# arduinoModuleLB.net
KiCad netlist of a schematic drawn in EAGLE
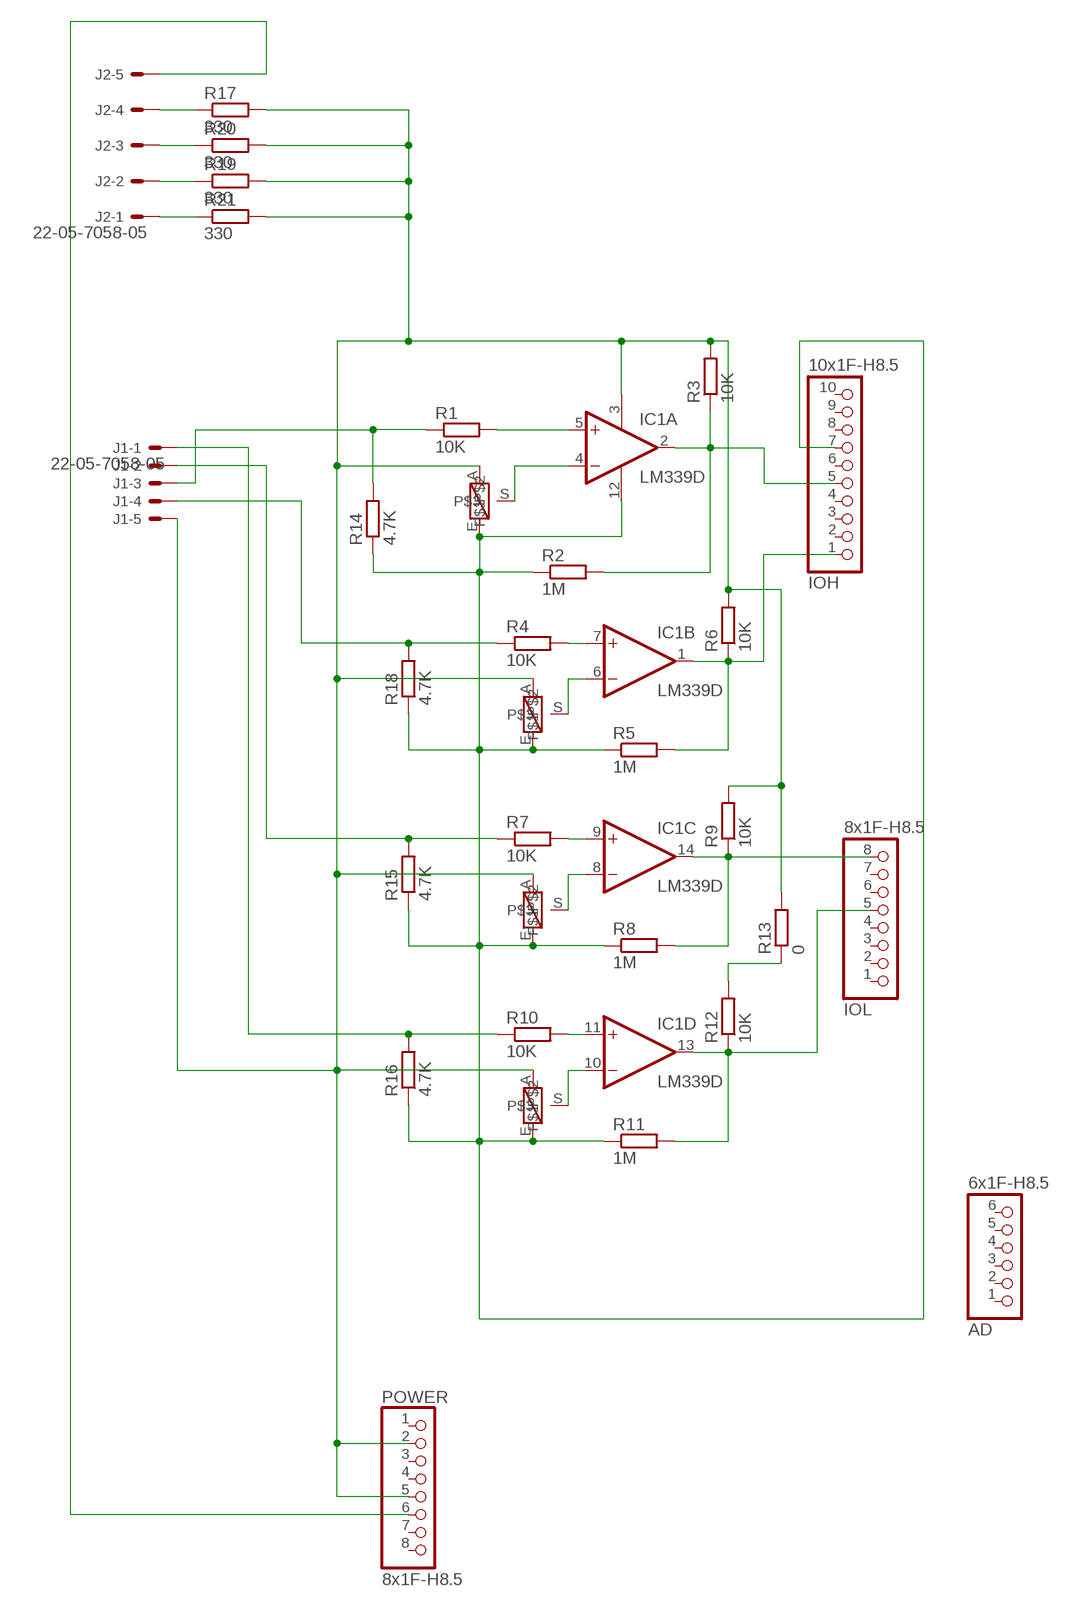
[diagram p0: schematic, sheet 1]

(export (version "E")
  (design (tool "Eeschema 10.0.6"))
  (components
    (comp (ref "AD")
      (value "6x1F-H8.5")
      (footprint "eagle-import:SMARTPRJ_1X06")
      (libsource (lib "eagle-import") (part "SMARTPRJ_PINHD-1X6"))
    )
    (comp (ref "IC1")
      (value "LM339D")
      (footprint "eagle-import:SO14")
      (libsource (lib "eagle-import") (part "LM339D"))
    )
    (comp (ref "IOH")
      (value "10x1F-H8.5")
      (footprint "eagle-import:SMARTPRJ_1X10")
      (libsource (lib "eagle-import") (part "SMARTPRJ_PINHD-1X10_ARD"))
    )
    (comp (ref "IOL")
      (value "8x1F-H8.5")
      (footprint "eagle-import:SMARTPRJ_1X08")
      (libsource (lib "eagle-import") (part "SMARTPRJ_PINHD-1X8"))
    )
    (comp (ref "J1")
      (value "22-05-7058-05")
      (footprint "eagle-import:7395-05")
      (libsource (lib "eagle-import") (part "22-?-0505-7058"))
    )
    (comp (ref "J2")
      (value "22-05-7058-05")
      (footprint "eagle-import:7395-05")
      (libsource (lib "eagle-import") (part "22-?-0505-7058"))
    )
    (comp (ref "POWER")
      (value "8x1F-H8.5")
      (footprint "eagle-import:SMARTPRJ_1X08")
      (libsource (lib "eagle-import") (part "SMARTPRJ_PINHD-1X8"))
    )
    (comp (ref "R1")
      (value "10K")
      (footprint "eagle-import:R0603")
      (libsource (lib "eagle-import") (part "R-EU_R0603"))
    )
    (comp (ref "R2")
      (value "1M")
      (footprint "eagle-import:R0603")
      (libsource (lib "eagle-import") (part "R-EU_R0603"))
    )
    (comp (ref "R3")
      (value "10K")
      (footprint "eagle-import:R0603")
      (libsource (lib "eagle-import") (part "R-EU_R0603"))
    )
    (comp (ref "R4")
      (value "10K")
      (footprint "eagle-import:R0603")
      (libsource (lib "eagle-import") (part "R-EU_R0603"))
    )
    (comp (ref "R5")
      (value "1M")
      (footprint "eagle-import:R0603")
      (libsource (lib "eagle-import") (part "R-EU_R0603"))
    )
    (comp (ref "R6")
      (value "10K")
      (footprint "eagle-import:R0603")
      (libsource (lib "eagle-import") (part "R-EU_R0603"))
    )
    (comp (ref "R7")
      (value "10K")
      (footprint "eagle-import:R0603")
      (libsource (lib "eagle-import") (part "R-EU_R0603"))
    )
    (comp (ref "R8")
      (value "1M")
      (footprint "eagle-import:R0603")
      (libsource (lib "eagle-import") (part "R-EU_R0603"))
    )
    (comp (ref "R9")
      (value "10K")
      (footprint "eagle-import:R0603")
      (libsource (lib "eagle-import") (part "R-EU_R0603"))
    )
    (comp (ref "R10")
      (value "10K")
      (footprint "eagle-import:R0603")
      (libsource (lib "eagle-import") (part "R-EU_R0603"))
    )
    (comp (ref "R11")
      (value "1M")
      (footprint "eagle-import:R0603")
      (libsource (lib "eagle-import") (part "R-EU_R0603"))
    )
    (comp (ref "R12")
      (value "10K")
      (footprint "eagle-import:R0603")
      (libsource (lib "eagle-import") (part "R-EU_R0603"))
    )
    (comp (ref "R13")
      (value "0")
      (footprint "eagle-import:0207_10")
      (libsource (lib "eagle-import") (part "R-EU_0207/10"))
    )
    (comp (ref "R14")
      (value "4.7K")
      (footprint "eagle-import:0207_10")
      (libsource (lib "eagle-import") (part "R-EU_0207/10"))
    )
    (comp (ref "R15")
      (value "4.7K")
      (footprint "eagle-import:0207_10")
      (libsource (lib "eagle-import") (part "R-EU_0207/10"))
    )
    (comp (ref "R16")
      (value "4.7K")
      (footprint "eagle-import:0207_10")
      (libsource (lib "eagle-import") (part "R-EU_0207/10"))
    )
    (comp (ref "R17")
      (value "330")
      (footprint "eagle-import:R0603")
      (libsource (lib "eagle-import") (part "R-EU_R0603"))
    )
    (comp (ref "R18")
      (value "4.7K")
      (footprint "eagle-import:0207_10")
      (libsource (lib "eagle-import") (part "R-EU_0207/10"))
    )
    (comp (ref "R19")
      (value "330")
      (footprint "eagle-import:R0603")
      (libsource (lib "eagle-import") (part "R-EU_R0603"))
    )
    (comp (ref "R20")
      (value "330")
      (footprint "eagle-import:R0603")
      (libsource (lib "eagle-import") (part "R-EU_R0603"))
    )
    (comp (ref "R21")
      (value "330")
      (footprint "eagle-import:R0603")
      (libsource (lib "eagle-import") (part "R-EU_R0603"))
    )
    (comp (ref "U$3")
      (value "M64P103KB40")
      (footprint "eagle-import:M64P")
      (libsource (lib "eagle-import") (part "M64P103KB40"))
    )
    (comp (ref "U$4")
      (value "M64P103KB40")
      (footprint "eagle-import:M64P")
      (libsource (lib "eagle-import") (part "M64P103KB40"))
    )
    (comp (ref "U$5")
      (value "M64P103KB40")
      (footprint "eagle-import:M64P")
      (libsource (lib "eagle-import") (part "M64P103KB40"))
    )
    (comp (ref "U$6")
      (value "M64P103KB40")
      (footprint "eagle-import:M64P")
      (libsource (lib "eagle-import") (part "M64P103KB40"))
    )
  )
  (nets
    (net (code "1") (name "Net-(IC1A-+IN)") (class "Default")
      (node (ref "IC1") (pin "5") (pinfunction "+IN_5") (pintype "input"))
      (node (ref "R1") (pin "2") (pinfunction "2_2") (pintype "passive"))
    )
    (net (code "2") (name "Net-(IC1A--IN)") (class "Default")
      (node (ref "IC1") (pin "4") (pinfunction "-IN_4") (pintype "input"))
      (node (ref "U$4") (pin "S") (pinfunction "P$3_S") (pintype "bidirectional"))
    )
    (net (code "3") (name "Net-(IC1A-OUT)") (class "Default")
      (node (ref "IC1") (pin "2") (pinfunction "OUT_2") (pintype "open_collector"))
      (node (ref "IOH") (pin "5") (pinfunction "5_5") (pintype "passive"))
      (node (ref "R2") (pin "2") (pinfunction "2_2") (pintype "passive"))
      (node (ref "R3") (pin "1") (pinfunction "1_1") (pintype "passive"))
    )
    (net (code "4") (name "Net-(IC1B-+IN)") (class "Default")
      (node (ref "IC1") (pin "7") (pinfunction "+IN_7") (pintype "input"))
      (node (ref "R4") (pin "2") (pinfunction "2_2") (pintype "passive"))
    )
    (net (code "5") (name "Net-(IC1B--IN)") (class "Default")
      (node (ref "IC1") (pin "6") (pinfunction "-IN_6") (pintype "input"))
      (node (ref "U$3") (pin "S") (pinfunction "P$3_S") (pintype "bidirectional"))
    )
    (net (code "6") (name "Net-(IC1B-OUT)") (class "Default")
      (node (ref "IC1") (pin "1") (pinfunction "OUT_1") (pintype "open_collector"))
      (node (ref "IOH") (pin "1") (pinfunction "1_1") (pintype "passive"))
      (node (ref "R5") (pin "2") (pinfunction "2_2") (pintype "passive"))
      (node (ref "R6") (pin "1") (pinfunction "1_1") (pintype "passive"))
    )
    (net (code "7") (name "Net-(IC1C-+IN)") (class "Default")
      (node (ref "IC1") (pin "9") (pinfunction "+IN_9") (pintype "input"))
      (node (ref "R7") (pin "2") (pinfunction "2_2") (pintype "passive"))
    )
    (net (code "8") (name "Net-(IC1C--IN)") (class "Default")
      (node (ref "IC1") (pin "8") (pinfunction "-IN_8") (pintype "input"))
      (node (ref "U$5") (pin "S") (pinfunction "P$3_S") (pintype "bidirectional"))
    )
    (net (code "9") (name "Net-(IC1C-OUT)") (class "Default")
      (node (ref "IC1") (pin "14") (pinfunction "OUT_14") (pintype "open_collector"))
      (node (ref "IOL") (pin "8") (pinfunction "8_8") (pintype "passive"))
      (node (ref "R8") (pin "2") (pinfunction "2_2") (pintype "passive"))
      (node (ref "R9") (pin "1") (pinfunction "1_1") (pintype "passive"))
    )
    (net (code "10") (name "Net-(IC1D-+IN)") (class "Default")
      (node (ref "IC1") (pin "11") (pinfunction "+IN_11") (pintype "input"))
      (node (ref "R10") (pin "2") (pinfunction "2_2") (pintype "passive"))
    )
    (net (code "11") (name "Net-(IC1D--IN)") (class "Default")
      (node (ref "IC1") (pin "10") (pinfunction "-IN_10") (pintype "input"))
      (node (ref "U$6") (pin "S") (pinfunction "P$3_S") (pintype "bidirectional"))
    )
    (net (code "12") (name "Net-(IC1D-OUT)") (class "Default")
      (node (ref "IC1") (pin "13") (pinfunction "OUT_13") (pintype "open_collector"))
      (node (ref "IOL") (pin "5") (pinfunction "5_5") (pintype "passive"))
      (node (ref "R11") (pin "2") (pinfunction "2_2") (pintype "passive"))
      (node (ref "R12") (pin "1") (pinfunction "1_1") (pintype "passive"))
    )
    (net (code "13") (name "Net-(IC1E-GND)") (class "Default")
      (node (ref "IC1") (pin "12") (pinfunction "GND_12") (pintype "power_in"))
      (node (ref "IOH") (pin "7") (pinfunction "7_7") (pintype "passive"))
      (node (ref "R11") (pin "1") (pinfunction "1_1") (pintype "passive"))
      (node (ref "R14") (pin "1") (pinfunction "1_1") (pintype "passive"))
      (node (ref "R15") (pin "1") (pinfunction "1_1") (pintype "passive"))
      (node (ref "R16") (pin "1") (pinfunction "1_1") (pintype "passive"))
      (node (ref "R18") (pin "1") (pinfunction "1_1") (pintype "passive"))
      (node (ref "R2") (pin "1") (pinfunction "1_1") (pintype "passive"))
      (node (ref "R5") (pin "1") (pinfunction "1_1") (pintype "passive"))
      (node (ref "R8") (pin "1") (pinfunction "1_1") (pintype "passive"))
      (node (ref "U$3") (pin "E") (pinfunction "P$2_E") (pintype "bidirectional"))
      (node (ref "U$4") (pin "E") (pinfunction "P$2_E") (pintype "bidirectional"))
      (node (ref "U$5") (pin "E") (pinfunction "P$2_E") (pintype "bidirectional"))
      (node (ref "U$6") (pin "E") (pinfunction "P$2_E") (pintype "bidirectional"))
    )
    (net (code "14") (name "Net-(IC1E-V+)") (class "Default")
      (node (ref "IC1") (pin "3") (pinfunction "V+_3") (pintype "power_in"))
      (node (ref "J1") (pin "5") (pinfunction "S_5") (pintype "passive"))
      (node (ref "POWER") (pin "2") (pinfunction "2_2") (pintype "passive"))
      (node (ref "POWER") (pin "5") (pinfunction "5_5") (pintype "passive"))
      (node (ref "R13") (pin "2") (pinfunction "2_2") (pintype "passive"))
      (node (ref "R17") (pin "2") (pinfunction "2_2") (pintype "passive"))
      (node (ref "R19") (pin "2") (pinfunction "2_2") (pintype "passive"))
      (node (ref "R20") (pin "2") (pinfunction "2_2") (pintype "passive"))
      (node (ref "R21") (pin "2") (pinfunction "2_2") (pintype "passive"))
      (node (ref "R3") (pin "2") (pinfunction "2_2") (pintype "passive"))
      (node (ref "R6") (pin "2") (pinfunction "2_2") (pintype "passive"))
      (node (ref "R9") (pin "2") (pinfunction "2_2") (pintype "passive"))
      (node (ref "U$3") (pin "A") (pinfunction "P$1_A") (pintype "bidirectional"))
      (node (ref "U$4") (pin "A") (pinfunction "P$1_A") (pintype "bidirectional"))
      (node (ref "U$5") (pin "A") (pinfunction "P$1_A") (pintype "bidirectional"))
      (node (ref "U$6") (pin "A") (pinfunction "P$1_A") (pintype "bidirectional"))
    )
    (net (code "15") (name "Net-(J1A-S)") (class "Default")
      (node (ref "J1") (pin "1") (pinfunction "S_1") (pintype "passive"))
      (node (ref "R10") (pin "1") (pinfunction "1_1") (pintype "passive"))
      (node (ref "R16") (pin "2") (pinfunction "2_2") (pintype "passive"))
    )
    (net (code "16") (name "Net-(J1B-S)") (class "Default")
      (node (ref "J1") (pin "2") (pinfunction "S_2") (pintype "passive"))
      (node (ref "R15") (pin "2") (pinfunction "2_2") (pintype "passive"))
      (node (ref "R7") (pin "1") (pinfunction "1_1") (pintype "passive"))
    )
    (net (code "17") (name "Net-(J1C-S)") (class "Default")
      (node (ref "J1") (pin "3") (pinfunction "S_3") (pintype "passive"))
      (node (ref "R1") (pin "1") (pinfunction "1_1") (pintype "passive"))
      (node (ref "R14") (pin "2") (pinfunction "2_2") (pintype "passive"))
    )
    (net (code "18") (name "Net-(J1D-S)") (class "Default")
      (node (ref "J1") (pin "4") (pinfunction "S_4") (pintype "passive"))
      (node (ref "R18") (pin "2") (pinfunction "2_2") (pintype "passive"))
      (node (ref "R4") (pin "1") (pinfunction "1_1") (pintype "passive"))
    )
    (net (code "19") (name "Net-(J2A-S)") (class "Default")
      (node (ref "J2") (pin "1") (pinfunction "S_1") (pintype "passive"))
      (node (ref "R21") (pin "1") (pinfunction "1_1") (pintype "passive"))
    )
    (net (code "20") (name "Net-(J2B-S)") (class "Default")
      (node (ref "J2") (pin "2") (pinfunction "S_2") (pintype "passive"))
      (node (ref "R19") (pin "1") (pinfunction "1_1") (pintype "passive"))
    )
    (net (code "21") (name "Net-(J2C-S)") (class "Default")
      (node (ref "J2") (pin "3") (pinfunction "S_3") (pintype "passive"))
      (node (ref "R20") (pin "1") (pinfunction "1_1") (pintype "passive"))
    )
    (net (code "22") (name "Net-(J2D-S)") (class "Default")
      (node (ref "J2") (pin "4") (pinfunction "S_4") (pintype "passive"))
      (node (ref "R17") (pin "1") (pinfunction "1_1") (pintype "passive"))
    )
    (net (code "23") (name "Net-(J2E-S)") (class "Default")
      (node (ref "J2") (pin "5") (pinfunction "S_5") (pintype "passive"))
      (node (ref "POWER") (pin "6") (pinfunction "6_6") (pintype "passive"))
    )
    (net (code "24") (name "Net-(R12-Pad2)") (class "Default")
      (node (ref "R12") (pin "2") (pinfunction "2_2") (pintype "passive"))
      (node (ref "R13") (pin "1") (pinfunction "1_1") (pintype "passive"))
    )
    (net (code "25") (name "unconnected-(AD-Pad1)") (class "Default")
      (node (ref "AD") (pin "1") (pinfunction "1_1") (pintype "passive"))
    )
    (net (code "26") (name "unconnected-(AD-Pad2)") (class "Default")
      (node (ref "AD") (pin "2") (pinfunction "2_2") (pintype "passive"))
    )
    (net (code "27") (name "unconnected-(AD-Pad3)") (class "Default")
      (node (ref "AD") (pin "3") (pinfunction "3_3") (pintype "passive"))
    )
    (net (code "28") (name "unconnected-(AD-Pad4)") (class "Default")
      (node (ref "AD") (pin "4") (pinfunction "4_4") (pintype "passive"))
    )
    (net (code "29") (name "unconnected-(AD-Pad5)") (class "Default")
      (node (ref "AD") (pin "5") (pinfunction "5_5") (pintype "passive"))
    )
    (net (code "30") (name "unconnected-(AD-Pad6)") (class "Default")
      (node (ref "AD") (pin "6") (pinfunction "6_6") (pintype "passive"))
    )
    (net (code "31") (name "unconnected-(IOH-Pad2)") (class "Default")
      (node (ref "IOH") (pin "2") (pinfunction "2_2") (pintype "passive"))
    )
    (net (code "32") (name "unconnected-(IOH-Pad3)") (class "Default")
      (node (ref "IOH") (pin "3") (pinfunction "3_3") (pintype "passive"))
    )
    (net (code "33") (name "unconnected-(IOH-Pad4)") (class "Default")
      (node (ref "IOH") (pin "4") (pinfunction "4_4") (pintype "passive"))
    )
    (net (code "34") (name "unconnected-(IOH-Pad6)") (class "Default")
      (node (ref "IOH") (pin "6") (pinfunction "6_6") (pintype "passive"))
    )
    (net (code "35") (name "unconnected-(IOH-Pad8)") (class "Default")
      (node (ref "IOH") (pin "8") (pinfunction "8_8") (pintype "passive"))
    )
    (net (code "36") (name "unconnected-(IOH-Pad9)") (class "Default")
      (node (ref "IOH") (pin "9") (pinfunction "9_9") (pintype "passive"))
    )
    (net (code "37") (name "unconnected-(IOH-Pad10)") (class "Default")
      (node (ref "IOH") (pin "10") (pinfunction "10_10") (pintype "passive"))
    )
    (net (code "38") (name "unconnected-(IOL-Pad1)") (class "Default")
      (node (ref "IOL") (pin "1") (pinfunction "1_1") (pintype "passive"))
    )
    (net (code "39") (name "unconnected-(IOL-Pad2)") (class "Default")
      (node (ref "IOL") (pin "2") (pinfunction "2_2") (pintype "passive"))
    )
    (net (code "40") (name "unconnected-(IOL-Pad3)") (class "Default")
      (node (ref "IOL") (pin "3") (pinfunction "3_3") (pintype "passive"))
    )
    (net (code "41") (name "unconnected-(IOL-Pad4)") (class "Default")
      (node (ref "IOL") (pin "4") (pinfunction "4_4") (pintype "passive"))
    )
    (net (code "42") (name "unconnected-(IOL-Pad6)") (class "Default")
      (node (ref "IOL") (pin "6") (pinfunction "6_6") (pintype "passive"))
    )
    (net (code "43") (name "unconnected-(IOL-Pad7)") (class "Default")
      (node (ref "IOL") (pin "7") (pinfunction "7_7") (pintype "passive"))
    )
    (net (code "44") (name "unconnected-(POWER-Pad1)") (class "Default")
      (node (ref "POWER") (pin "1") (pinfunction "1_1") (pintype "passive"))
    )
    (net (code "45") (name "unconnected-(POWER-Pad3)") (class "Default")
      (node (ref "POWER") (pin "3") (pinfunction "3_3") (pintype "passive"))
    )
    (net (code "46") (name "unconnected-(POWER-Pad4)") (class "Default")
      (node (ref "POWER") (pin "4") (pinfunction "4_4") (pintype "passive"))
    )
    (net (code "47") (name "unconnected-(POWER-Pad7)") (class "Default")
      (node (ref "POWER") (pin "7") (pinfunction "7_7") (pintype "passive"))
    )
    (net (code "48") (name "unconnected-(POWER-Pad8)") (class "Default")
      (node (ref "POWER") (pin "8") (pinfunction "8_8") (pintype "passive"))
    )
  )
)
